# SCH_Loader.net
KiCad netlist of a schematic drawn in EasyEDA
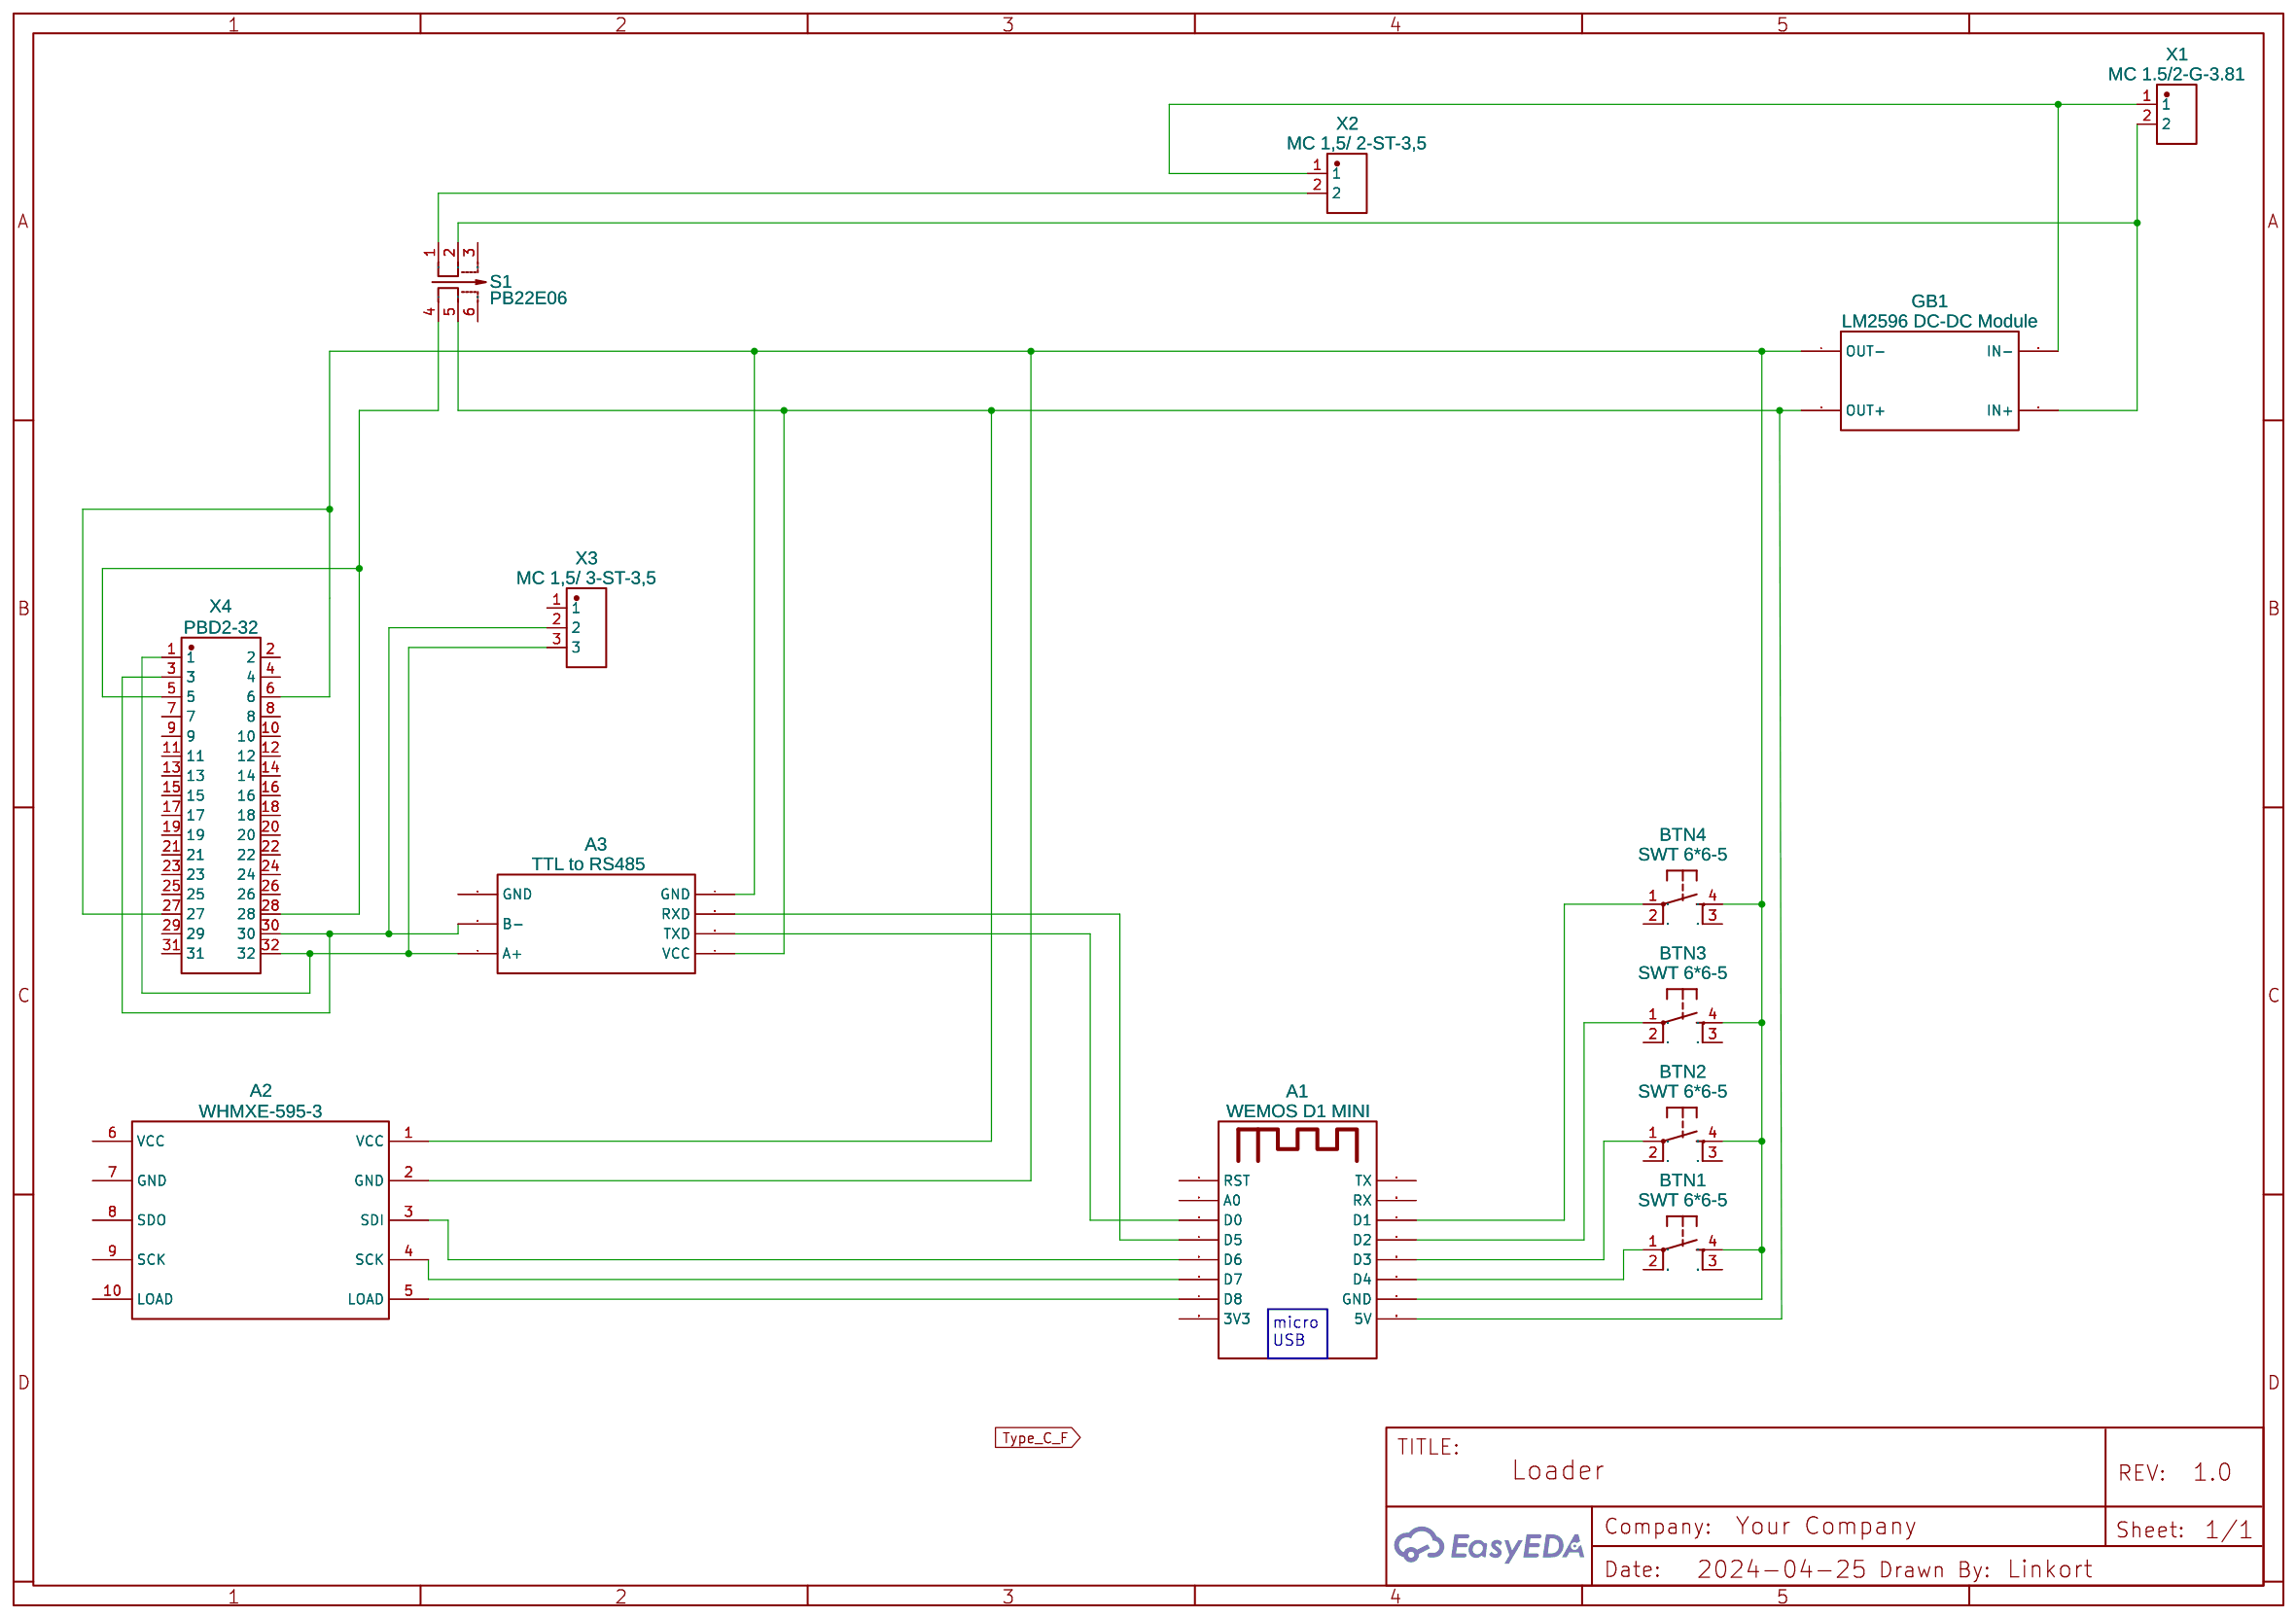
[diagram p0: schematic sheet]

(export (version "E")
  (design (tool "Eeschema 10.0.6"))
  (components
    (comp (ref "A1")
      (value "WEMOS D1 MINI")
      (fields (field (name "Manufacturer Part") "D1 Mini") (field (name "Manufacturer") "Wemos"))
      (libsource (lib "") (part "WEMOS D1 MINI COPY"))
    )
    (comp (ref "A2")
      (value "WHMXE-595-3")
      (fields (field (name "Manufacturer Part") "WHMXE-595"))
      (libsource (lib "") (part "WHMXE-595"))
    )
    (comp (ref "A3") (value "TTL to RS485") (libsource (lib "") (part "HW-519-RS485")))
    (comp (ref "BTN1") (value "SWT 6*6-5") (libsource (lib "") (part "TACTILE_BUTTON_SMD")))
    (comp (ref "BTN2") (value "SWT 6*6-5") (libsource (lib "") (part "TACTILE_BUTTON_SMD")))
    (comp (ref "BTN3") (value "SWT 6*6-5") (libsource (lib "") (part "TACTILE_BUTTON_SMD")))
    (comp (ref "BTN4") (value "SWT 6*6-5") (libsource (lib "") (part "TACTILE_BUTTON_SMD")))
    (comp (ref "GB1")
      (value "LM2596 DC-DC Module")
      (fields (field (name "Manufacturer Part") "LM2596-MODULE"))
      (libsource (lib "") (part "LM2596-MODULE COPY"))
    )
    (comp (ref "S1")
      (value "PB22E06")
      (fields
        (field (name "Manufacturer Part") "PB22E06371-0625")
        (field (name "Manufacturer") "GANGYUAN(港源)")
      )
      (libsource (lib "") (part "PB22E06071"))
    )
    (comp (ref "X1")
      (value "MC 1.5/2-G-3.81")
      (fields
        (field (name "Manufacturer Part") "1803277")
        (field (name "Manufacturer") "Phoenix Contact(菲尼克斯)")
      )
      (libsource (lib "") (part "1803277"))
    )
    (comp (ref "X2")
      (value "MC 1,5/ 2-ST-3,5")
      (fields (field (name "Manufacturer Part") "2PIN(2MM)-1"))
      (libsource (lib "") (part "2PIN(2MM)-1"))
    )
    (comp (ref "X3")
      (value "MC 1,5/ 3-ST-3,5")
      (fields (field (name "Manufacturer Part") "3PIN_POGO_2.54"))
      (libsource (lib "") (part "3PIN_POGO_2.54"))
    )
    (comp (ref "X4")
      (value "PBD2-32")
      (fields
        (field (name "Manufacturer Part") "PZ254-2-16-Z-2.5-G1")
        (field (name "Manufacturer") "HCTL(华灿天禄)")
      )
      (libsource (lib "") (part "PZ254-2-16-Z-2.5-G1 COPY"))
    )
  )
  (nets
    (net (code "1") (name "Net-(A1-5V)") (class "Default")
      (node (ref "A1") (pin "16") (pinfunction "5V_16") (pintype "unspecified"))
      (node (ref "A2") (pin "1") (pinfunction "VCC_1") (pintype "unspecified"))
      (node (ref "A3") (pin "4") (pinfunction "VCC_4") (pintype "unspecified"))
      (node (ref "GB1") (pin "3") (pinfunction "OUT+_3") (pintype "unspecified"))
      (node (ref "S1") (pin "5") (pinfunction "5_5") (pintype "unspecified"))
    )
    (net (code "2") (name "Net-(A1-D0)") (class "Default")
      (node (ref "A1") (pin "3") (pinfunction "D0_3") (pintype "unspecified"))
      (node (ref "A3") (pin "5") (pinfunction "TXD_5") (pintype "unspecified"))
    )
    (net (code "3") (name "Net-(A1-D1)") (class "Default")
      (node (ref "A1") (pin "11") (pinfunction "D1_11") (pintype "unspecified"))
      (node (ref "BTN4") (pin "1") (pinfunction "SWA1_1") (pintype "bidirectional"))
    )
    (net (code "4") (name "Net-(A1-D2)") (class "Default")
      (node (ref "A1") (pin "12") (pinfunction "D2_12") (pintype "unspecified"))
      (node (ref "BTN3") (pin "1") (pinfunction "SWA1_1") (pintype "bidirectional"))
    )
    (net (code "5") (name "Net-(A1-D3)") (class "Default")
      (node (ref "A1") (pin "13") (pinfunction "D3_13") (pintype "unspecified"))
      (node (ref "BTN2") (pin "1") (pinfunction "SWA1_1") (pintype "bidirectional"))
    )
    (net (code "6") (name "Net-(A1-D4)") (class "Default")
      (node (ref "A1") (pin "14") (pinfunction "D4_14") (pintype "unspecified"))
      (node (ref "BTN1") (pin "1") (pinfunction "SWA1_1") (pintype "bidirectional"))
    )
    (net (code "7") (name "Net-(A1-D5)") (class "Default")
      (node (ref "A1") (pin "4") (pinfunction "D5_4") (pintype "unspecified"))
      (node (ref "A3") (pin "6") (pinfunction "RXD_6") (pintype "unspecified"))
    )
    (net (code "8") (name "Net-(A1-D6)") (class "Default")
      (node (ref "A1") (pin "5") (pinfunction "D6_5") (pintype "unspecified"))
      (node (ref "A2") (pin "3") (pinfunction "SDI_3") (pintype "unspecified"))
    )
    (net (code "9") (name "Net-(A1-D7)") (class "Default")
      (node (ref "A1") (pin "6") (pinfunction "D7_6") (pintype "unspecified"))
      (node (ref "A2") (pin "4") (pinfunction "SCK_4") (pintype "unspecified"))
    )
    (net (code "10") (name "Net-(A1-D8)") (class "Default")
      (node (ref "A1") (pin "7") (pinfunction "D8_7") (pintype "unspecified"))
      (node (ref "A2") (pin "5") (pinfunction "LOAD_5") (pintype "unspecified"))
    )
    (net (code "11") (name "Net-(A1-GND)") (class "Default")
      (node (ref "A1") (pin "15") (pinfunction "GND_15") (pintype "unspecified"))
      (node (ref "A2") (pin "2") (pinfunction "GND_2") (pintype "unspecified"))
      (node (ref "A3") (pin "7") (pinfunction "GND_7") (pintype "unspecified"))
      (node (ref "BTN1") (pin "4") (pinfunction "SWA2_4") (pintype "bidirectional"))
      (node (ref "BTN2") (pin "4") (pinfunction "SWA2_4") (pintype "bidirectional"))
      (node (ref "BTN3") (pin "4") (pinfunction "SWA2_4") (pintype "bidirectional"))
      (node (ref "BTN4") (pin "4") (pinfunction "SWA2_4") (pintype "bidirectional"))
      (node (ref "GB1") (pin "4") (pinfunction "OUT-_4") (pintype "unspecified"))
      (node (ref "X4") (pin "27") (pinfunction "27_27") (pintype "unspecified"))
      (node (ref "X4") (pin "6") (pinfunction "6_6") (pintype "unspecified"))
    )
    (net (code "12") (name "Net-(A3-A+)") (class "Default")
      (node (ref "A3") (pin "1") (pinfunction "A+_1") (pintype "unspecified"))
      (node (ref "X3") (pin "3") (pinfunction "3_3") (pintype "unspecified"))
      (node (ref "X4") (pin "1") (pinfunction "1_1") (pintype "unspecified"))
      (node (ref "X4") (pin "32") (pinfunction "32_32") (pintype "unspecified"))
    )
    (net (code "13") (name "Net-(A3-B-)") (class "Default")
      (node (ref "A3") (pin "2") (pinfunction "B-_2") (pintype "unspecified"))
      (node (ref "X3") (pin "2") (pinfunction "2_2") (pintype "unspecified"))
      (node (ref "X4") (pin "3") (pinfunction "3_3") (pintype "unspecified"))
      (node (ref "X4") (pin "30") (pinfunction "30_30") (pintype "unspecified"))
    )
    (net (code "14") (name "Net-(GB1-IN+)") (class "Default")
      (node (ref "GB1") (pin "1") (pinfunction "IN+_1") (pintype "unspecified"))
      (node (ref "S1") (pin "2") (pinfunction "2_2") (pintype "unspecified"))
      (node (ref "X1") (pin "2") (pinfunction "2_2") (pintype "unspecified"))
    )
    (net (code "15") (name "Net-(GB1-IN-)") (class "Default")
      (node (ref "GB1") (pin "2") (pinfunction "IN-_2") (pintype "unspecified"))
      (node (ref "X1") (pin "1") (pinfunction "1_1") (pintype "unspecified"))
      (node (ref "X2") (pin "1") (pinfunction "1_1") (pintype "unspecified"))
    )
    (net (code "16") (name "Net-(S1-Pad1)") (class "Default")
      (node (ref "S1") (pin "1") (pinfunction "1_1") (pintype "unspecified"))
      (node (ref "X2") (pin "2") (pinfunction "2_2") (pintype "unspecified"))
    )
    (net (code "17") (name "Net-(S1-Pad4)") (class "Default")
      (node (ref "S1") (pin "4") (pinfunction "4_4") (pintype "unspecified"))
      (node (ref "X4") (pin "28") (pinfunction "28_28") (pintype "unspecified"))
      (node (ref "X4") (pin "5") (pinfunction "5_5") (pintype "unspecified"))
    )
    (net (code "19") (name "unconnected-(A1-3V3-Pad8)") (class "Default")
      (node (ref "A1") (pin "8") (pinfunction "3V3_8") (pintype "unspecified"))
    )
    (net (code "20") (name "unconnected-(A1-A0-Pad2)") (class "Default")
      (node (ref "A1") (pin "2") (pinfunction "A0_2") (pintype "unspecified"))
    )
    (net (code "21") (name "unconnected-(A1-RST-Pad1)") (class "Default")
      (node (ref "A1") (pin "1") (pinfunction "RST_1") (pintype "unspecified"))
    )
    (net (code "22") (name "unconnected-(A1-RX-Pad10)") (class "Default")
      (node (ref "A1") (pin "10") (pinfunction "RX_10") (pintype "unspecified"))
    )
    (net (code "23") (name "unconnected-(A1-TX-Pad9)") (class "Default")
      (node (ref "A1") (pin "9") (pinfunction "TX_9") (pintype "unspecified"))
    )
    (net (code "24") (name "unconnected-(A2-GND-Pad7)") (class "Default")
      (node (ref "A2") (pin "7") (pinfunction "GND_7") (pintype "unspecified"))
    )
    (net (code "25") (name "unconnected-(A2-LOAD-Pad10)") (class "Default")
      (node (ref "A2") (pin "10") (pinfunction "LOAD_10") (pintype "unspecified"))
    )
    (net (code "26") (name "unconnected-(A2-SCK-Pad9)") (class "Default")
      (node (ref "A2") (pin "9") (pinfunction "SCK_9") (pintype "unspecified"))
    )
    (net (code "27") (name "unconnected-(A2-SDO-Pad8)") (class "Default")
      (node (ref "A2") (pin "8") (pinfunction "SDO_8") (pintype "unspecified"))
    )
    (net (code "28") (name "unconnected-(A2-VCC-Pad6)") (class "Default")
      (node (ref "A2") (pin "6") (pinfunction "VCC_6") (pintype "unspecified"))
    )
    (net (code "29") (name "unconnected-(A3-GND-Pad3)") (class "Default")
      (node (ref "A3") (pin "3") (pinfunction "GND_3") (pintype "unspecified"))
    )
    (net (code "30") (name "unconnected-(BTN1-SWB1-Pad2)") (class "Default")
      (node (ref "BTN1") (pin "2") (pinfunction "SWB1_2") (pintype "bidirectional"))
    )
    (net (code "31") (name "unconnected-(BTN1-SWB2-Pad3)") (class "Default")
      (node (ref "BTN1") (pin "3") (pinfunction "SWB2_3") (pintype "bidirectional"))
    )
    (net (code "32") (name "unconnected-(BTN2-SWB1-Pad2)") (class "Default")
      (node (ref "BTN2") (pin "2") (pinfunction "SWB1_2") (pintype "bidirectional"))
    )
    (net (code "33") (name "unconnected-(BTN2-SWB2-Pad3)") (class "Default")
      (node (ref "BTN2") (pin "3") (pinfunction "SWB2_3") (pintype "bidirectional"))
    )
    (net (code "34") (name "unconnected-(BTN3-SWB1-Pad2)") (class "Default")
      (node (ref "BTN3") (pin "2") (pinfunction "SWB1_2") (pintype "bidirectional"))
    )
    (net (code "35") (name "unconnected-(BTN3-SWB2-Pad3)") (class "Default")
      (node (ref "BTN3") (pin "3") (pinfunction "SWB2_3") (pintype "bidirectional"))
    )
    (net (code "36") (name "unconnected-(BTN4-SWB1-Pad2)") (class "Default")
      (node (ref "BTN4") (pin "2") (pinfunction "SWB1_2") (pintype "bidirectional"))
    )
    (net (code "37") (name "unconnected-(BTN4-SWB2-Pad3)") (class "Default")
      (node (ref "BTN4") (pin "3") (pinfunction "SWB2_3") (pintype "bidirectional"))
    )
    (net (code "38") (name "unconnected-(S1-Pad3)") (class "Default")
      (node (ref "S1") (pin "3") (pinfunction "3_3") (pintype "unspecified"))
    )
    (net (code "39") (name "unconnected-(S1-Pad6)") (class "Default")
      (node (ref "S1") (pin "6") (pinfunction "6_6") (pintype "unspecified"))
    )
    (net (code "40") (name "unconnected-(X3-Pad1)") (class "Default")
      (node (ref "X3") (pin "1") (pinfunction "1_1") (pintype "unspecified"))
    )
    (net (code "41") (name "unconnected-(X4-Pad2)") (class "Default")
      (node (ref "X4") (pin "2") (pinfunction "2_2") (pintype "unspecified"))
    )
    (net (code "42") (name "unconnected-(X4-Pad4)") (class "Default")
      (node (ref "X4") (pin "4") (pinfunction "4_4") (pintype "unspecified"))
    )
    (net (code "43") (name "unconnected-(X4-Pad7)") (class "Default")
      (node (ref "X4") (pin "7") (pinfunction "7_7") (pintype "unspecified"))
    )
    (net (code "44") (name "unconnected-(X4-Pad8)") (class "Default")
      (node (ref "X4") (pin "8") (pinfunction "8_8") (pintype "unspecified"))
    )
    (net (code "45") (name "unconnected-(X4-Pad9)") (class "Default")
      (node (ref "X4") (pin "9") (pinfunction "9_9") (pintype "unspecified"))
    )
    (net (code "46") (name "unconnected-(X4-Pad10)") (class "Default")
      (node (ref "X4") (pin "10") (pinfunction "10_10") (pintype "unspecified"))
    )
    (net (code "47") (name "unconnected-(X4-Pad11)") (class "Default")
      (node (ref "X4") (pin "11") (pinfunction "11_11") (pintype "unspecified"))
    )
    (net (code "48") (name "unconnected-(X4-Pad12)") (class "Default")
      (node (ref "X4") (pin "12") (pinfunction "12_12") (pintype "unspecified"))
    )
    (net (code "49") (name "unconnected-(X4-Pad13)") (class "Default")
      (node (ref "X4") (pin "13") (pinfunction "13_13") (pintype "unspecified"))
    )
    (net (code "50") (name "unconnected-(X4-Pad14)") (class "Default")
      (node (ref "X4") (pin "14") (pinfunction "14_14") (pintype "unspecified"))
    )
    (net (code "51") (name "unconnected-(X4-Pad15)") (class "Default")
      (node (ref "X4") (pin "15") (pinfunction "15_15") (pintype "unspecified"))
    )
    (net (code "52") (name "unconnected-(X4-Pad16)") (class "Default")
      (node (ref "X4") (pin "16") (pinfunction "16_16") (pintype "unspecified"))
    )
    (net (code "53") (name "unconnected-(X4-Pad17)") (class "Default")
      (node (ref "X4") (pin "17") (pinfunction "17_17") (pintype "unspecified"))
    )
    (net (code "54") (name "unconnected-(X4-Pad18)") (class "Default")
      (node (ref "X4") (pin "18") (pinfunction "18_18") (pintype "unspecified"))
    )
    (net (code "55") (name "unconnected-(X4-Pad19)") (class "Default")
      (node (ref "X4") (pin "19") (pinfunction "19_19") (pintype "unspecified"))
    )
    (net (code "56") (name "unconnected-(X4-Pad20)") (class "Default")
      (node (ref "X4") (pin "20") (pinfunction "20_20") (pintype "unspecified"))
    )
    (net (code "57") (name "unconnected-(X4-Pad21)") (class "Default")
      (node (ref "X4") (pin "21") (pinfunction "21_21") (pintype "unspecified"))
    )
    (net (code "58") (name "unconnected-(X4-Pad22)") (class "Default")
      (node (ref "X4") (pin "22") (pinfunction "22_22") (pintype "unspecified"))
    )
    (net (code "59") (name "unconnected-(X4-Pad23)") (class "Default")
      (node (ref "X4") (pin "23") (pinfunction "23_23") (pintype "unspecified"))
    )
    (net (code "60") (name "unconnected-(X4-Pad24)") (class "Default")
      (node (ref "X4") (pin "24") (pinfunction "24_24") (pintype "unspecified"))
    )
    (net (code "61") (name "unconnected-(X4-Pad25)") (class "Default")
      (node (ref "X4") (pin "25") (pinfunction "25_25") (pintype "unspecified"))
    )
    (net (code "62") (name "unconnected-(X4-Pad26)") (class "Default")
      (node (ref "X4") (pin "26") (pinfunction "26_26") (pintype "unspecified"))
    )
    (net (code "63") (name "unconnected-(X4-Pad29)") (class "Default")
      (node (ref "X4") (pin "29") (pinfunction "29_29") (pintype "unspecified"))
    )
    (net (code "64") (name "unconnected-(X4-Pad31)") (class "Default")
      (node (ref "X4") (pin "31") (pinfunction "31_31") (pintype "unspecified"))
    )
  )
)
